# PlusBit_ExtraModule.net
KiCad netlist of a schematic drawn in Altium Designer
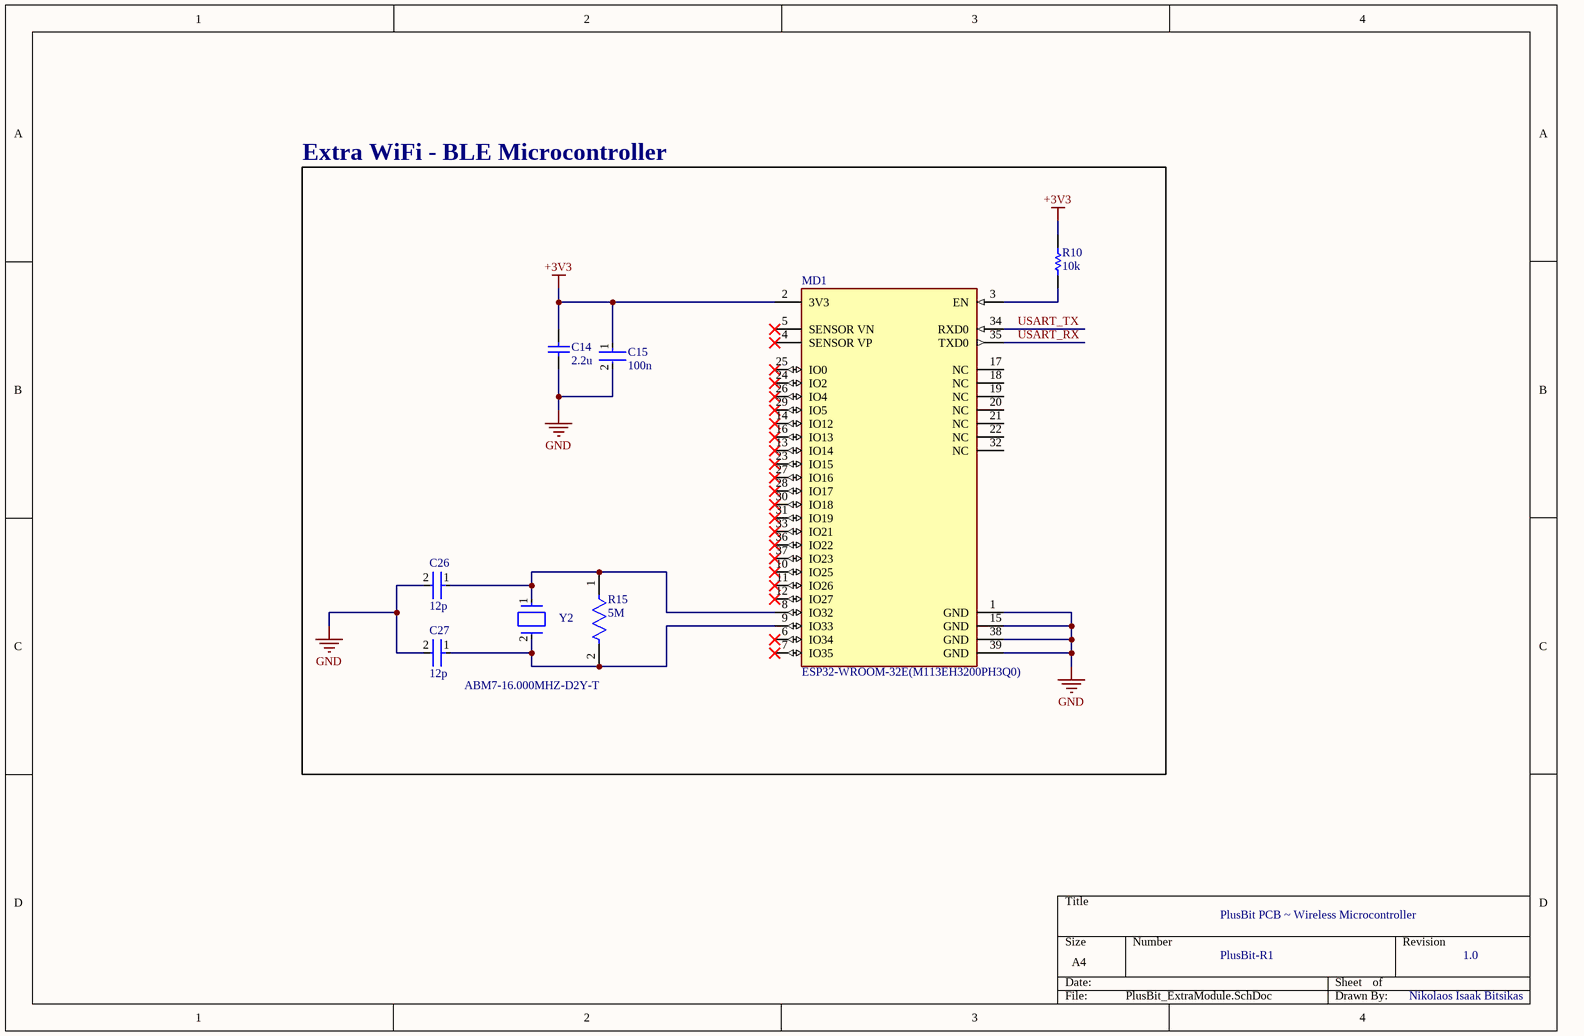
[diagram p0: PlusBit_ExtraModule.SchDoc]

(export (version "E")
  (design (tool "Eeschema 10.0.6"))
  (components
    (comp (ref "C14")
      (value "2.2u")
      (footprint "CAPC2013X145X50ML20T25")
      (fields (field (name "PART NUMBER") "C0805C225K9PACTU") (field (name "MANUFACTURER") "Kemet"))
      (libsource (lib "Altium Content Vault") (part "CAP"))
    )
    (comp (ref "C15")
      (value "100n")
      (footprint "FP-C0402-BB-MFG")
      (description "CAP CER 0.1UF 10V X5R 0402")
      (fields (field (name "MANUFACTURER") "Kemet") (field (name "TOLERANCE") "0.1"))
      (libsource (lib "Altium Content Vault") (part "b4654b650e69147ec39a6b967a45e02"))
    )
    (comp (ref "C26")
      (value "12p")
      (footprint "FP-C0402-BB-MFG")
      (description "CAP CER 12PF 50V C0G/NP0 0402")
      (fields
        (field (name "OCTOPART") "https://octopart.com/c0402c120j5gactu-kemet-141377")
        (field (name "MANUFACTURER PART NUMBER") "C0402C120J5GACTU")
      )
      (libsource (lib "Altium Content Vault") (part "b4654b650e69147ec39a6b967a45e02"))
    )
    (comp (ref "C27")
      (value "12p")
      (footprint "FP-C0402-BB-MFG")
      (description "CAP CER 12PF 50V C0G/NP0 0402")
      (fields
        (field (name "OCTOPART") "https://octopart.com/c0402c120j5gactu-kemet-141377")
        (field (name "MANUFACTURER PART NUMBER") "C0402C120J5GACTU")
      )
      (libsource (lib "Altium Content Vault") (part "b4654b650e69147ec39a6b967a45e02"))
    )
    (comp (ref "MD1")
      (value "ESP32-WROOM-32E(M113EH3200PH3Q0)")
      (footprint "FP-ESP32-WROOM-32E_M113EH-MFG")
      (description "RX TXRX MOD WIFI TRACE ANT SMD")
      (libsource (lib "Altium Content Vault") (part "a4840fbd16b6d3d8633d6b8ddc62dfb"))
    )
    (comp (ref "R10")
      (value "10k")
      (footprint "RESC1608X55X25ML10T15")
      (description "Resistor, 10 KOhm, +/- 5%, 100 mW, -55 to 155 degC, 0603 (1608 Metric), RoHS, Tape and Reel")
      (fields (field (name "MANUFACTURER") "Yageo") (field (name "TOLERANCE") "5%"))
      (libsource (lib "Altium Content Vault") (part "RES-2"))
    )
    (comp (ref "R15")
      (value "5M")
      (footprint "FP-WSLP0805-MFG")
      (description "RES 0.005 OHM 1% 1W 0805")
      (fields (field (name "TOLERANCE") "1%"))
      (libsource (lib "Altium Content Vault") (part "1029c3af85768c4190bb7ad29bc67b5"))
    )
    (comp (ref "Y2")
      (value "ABM7-16.000MHZ-D2Y-T")
      (footprint "FP-ABM7-MFG")
      (description "Crystal 16MHz ±20ppm 18pF SMD-2 6mm x 3.5mm")
      (fields (field (name "TOLERANCE") "20ppm"))
      (libsource (lib "Altium Content Vault") (part "c23a69dc6c9e2f18f2079038eb95dd1"))
    )
  )
  (nets
    (net (code "1") (name "+3V3") (class "Default")
      (node (ref "C14") (pin "2") (pinfunction "2_2") (pintype "passive"))
      (node (ref "C15") (pin "1") (pinfunction "1_1") (pintype "passive"))
      (node (ref "MD1") (pin "2") (pinfunction "3V3_2") (pintype "power_in"))
      (node (ref "R10") (pin "2") (pinfunction "2_2") (pintype "passive"))
    )
    (net (code "2") (name "/USART_RX") (class "Default")
      (node (ref "MD1") (pin "35") (pinfunction "TXD0_35") (pintype "output"))
    )
    (net (code "3") (name "/USART_TX") (class "Default")
      (node (ref "MD1") (pin "34") (pinfunction "RXD0_34") (pintype "input"))
    )
    (net (code "4") (name "GND") (class "Default")
      (node (ref "C14") (pin "1") (pinfunction "1_1") (pintype "passive"))
      (node (ref "C15") (pin "2") (pinfunction "2_2") (pintype "passive"))
      (node (ref "C26") (pin "2") (pinfunction "2_2") (pintype "passive"))
      (node (ref "C27") (pin "2") (pinfunction "2_2") (pintype "passive"))
      (node (ref "MD1") (pin "1") (pinfunction "GND_1") (pintype "power_in"))
      (node (ref "MD1") (pin "15") (pinfunction "GND_15") (pintype "power_in"))
      (node (ref "MD1") (pin "38") (pinfunction "GND_38") (pintype "power_in"))
      (node (ref "MD1") (pin "39") (pinfunction "GND_39") (pintype "power_in"))
    )
    (net (code "5") (name "Net-(MD1-EN)") (class "Default")
      (node (ref "MD1") (pin "3") (pinfunction "EN_3") (pintype "input"))
      (node (ref "R10") (pin "1") (pinfunction "1_1") (pintype "passive"))
    )
    (net (code "6") (name "Net-(MD1-IO32)") (class "Default")
      (node (ref "C26") (pin "1") (pinfunction "1_1") (pintype "passive"))
      (node (ref "MD1") (pin "8") (pinfunction "IO32_8") (pintype "bidirectional"))
      (node (ref "R15") (pin "1") (pinfunction "1_1") (pintype "passive"))
      (node (ref "Y2") (pin "1") (pinfunction "1_1") (pintype "passive"))
    )
    (net (code "7") (name "Net-(MD1-IO33)") (class "Default")
      (node (ref "C27") (pin "1") (pinfunction "1_1") (pintype "passive"))
      (node (ref "MD1") (pin "9") (pinfunction "IO33_9") (pintype "bidirectional"))
      (node (ref "R15") (pin "2") (pinfunction "2_2") (pintype "passive"))
      (node (ref "Y2") (pin "2") (pinfunction "2_2") (pintype "passive"))
    )
    (net (code "8") (name "unconnected-(MD1-IO0-Pad25)") (class "Default")
      (node (ref "MD1") (pin "25") (pinfunction "IO0_25") (pintype "bidirectional+no_connect"))
    )
    (net (code "9") (name "unconnected-(MD1-IO2-Pad24)") (class "Default")
      (node (ref "MD1") (pin "24") (pinfunction "IO2_24") (pintype "bidirectional+no_connect"))
    )
    (net (code "10") (name "unconnected-(MD1-IO4-Pad26)") (class "Default")
      (node (ref "MD1") (pin "26") (pinfunction "IO4_26") (pintype "bidirectional+no_connect"))
    )
    (net (code "11") (name "unconnected-(MD1-IO5-Pad29)") (class "Default")
      (node (ref "MD1") (pin "29") (pinfunction "IO5_29") (pintype "bidirectional+no_connect"))
    )
    (net (code "12") (name "unconnected-(MD1-IO12-Pad14)") (class "Default")
      (node (ref "MD1") (pin "14") (pinfunction "IO12_14") (pintype "bidirectional+no_connect"))
    )
    (net (code "13") (name "unconnected-(MD1-IO13-Pad16)") (class "Default")
      (node (ref "MD1") (pin "16") (pinfunction "IO13_16") (pintype "bidirectional+no_connect"))
    )
    (net (code "14") (name "unconnected-(MD1-IO14-Pad13)") (class "Default")
      (node (ref "MD1") (pin "13") (pinfunction "IO14_13") (pintype "bidirectional+no_connect"))
    )
    (net (code "15") (name "unconnected-(MD1-IO15-Pad23)") (class "Default")
      (node (ref "MD1") (pin "23") (pinfunction "IO15_23") (pintype "bidirectional+no_connect"))
    )
    (net (code "16") (name "unconnected-(MD1-IO16-Pad27)") (class "Default")
      (node (ref "MD1") (pin "27") (pinfunction "IO16_27") (pintype "bidirectional+no_connect"))
    )
    (net (code "17") (name "unconnected-(MD1-IO17-Pad28)") (class "Default")
      (node (ref "MD1") (pin "28") (pinfunction "IO17_28") (pintype "bidirectional+no_connect"))
    )
    (net (code "18") (name "unconnected-(MD1-IO18-Pad30)") (class "Default")
      (node (ref "MD1") (pin "30") (pinfunction "IO18_30") (pintype "bidirectional+no_connect"))
    )
    (net (code "19") (name "unconnected-(MD1-IO19-Pad31)") (class "Default")
      (node (ref "MD1") (pin "31") (pinfunction "IO19_31") (pintype "bidirectional+no_connect"))
    )
    (net (code "20") (name "unconnected-(MD1-IO21-Pad33)") (class "Default")
      (node (ref "MD1") (pin "33") (pinfunction "IO21_33") (pintype "bidirectional+no_connect"))
    )
    (net (code "21") (name "unconnected-(MD1-IO22-Pad36)") (class "Default")
      (node (ref "MD1") (pin "36") (pinfunction "IO22_36") (pintype "bidirectional+no_connect"))
    )
    (net (code "22") (name "unconnected-(MD1-IO23-Pad37)") (class "Default")
      (node (ref "MD1") (pin "37") (pinfunction "IO23_37") (pintype "bidirectional+no_connect"))
    )
    (net (code "23") (name "unconnected-(MD1-IO25-Pad10)") (class "Default")
      (node (ref "MD1") (pin "10") (pinfunction "IO25_10") (pintype "bidirectional+no_connect"))
    )
    (net (code "24") (name "unconnected-(MD1-IO26-Pad11)") (class "Default")
      (node (ref "MD1") (pin "11") (pinfunction "IO26_11") (pintype "bidirectional+no_connect"))
    )
    (net (code "25") (name "unconnected-(MD1-IO27-Pad12)") (class "Default")
      (node (ref "MD1") (pin "12") (pinfunction "IO27_12") (pintype "bidirectional+no_connect"))
    )
    (net (code "26") (name "unconnected-(MD1-IO34-Pad6)") (class "Default")
      (node (ref "MD1") (pin "6") (pinfunction "IO34_6") (pintype "bidirectional+no_connect"))
    )
    (net (code "27") (name "unconnected-(MD1-IO35-Pad7)") (class "Default")
      (node (ref "MD1") (pin "7") (pinfunction "IO35_7") (pintype "bidirectional+no_connect"))
    )
    (net (code "28") (name "unconnected-(MD1-NC-Pad17)") (class "Default")
      (node (ref "MD1") (pin "17") (pinfunction "NC_17") (pintype "passive"))
    )
    (net (code "29") (name "unconnected-(MD1-NC-Pad18)") (class "Default")
      (node (ref "MD1") (pin "18") (pinfunction "NC_18") (pintype "passive"))
    )
    (net (code "30") (name "unconnected-(MD1-NC-Pad19)") (class "Default")
      (node (ref "MD1") (pin "19") (pinfunction "NC_19") (pintype "passive"))
    )
    (net (code "31") (name "unconnected-(MD1-NC-Pad20)") (class "Default")
      (node (ref "MD1") (pin "20") (pinfunction "NC_20") (pintype "passive"))
    )
    (net (code "32") (name "unconnected-(MD1-NC-Pad21)") (class "Default")
      (node (ref "MD1") (pin "21") (pinfunction "NC_21") (pintype "passive"))
    )
    (net (code "33") (name "unconnected-(MD1-NC-Pad22)") (class "Default")
      (node (ref "MD1") (pin "22") (pinfunction "NC_22") (pintype "passive"))
    )
    (net (code "34") (name "unconnected-(MD1-NC-Pad32)") (class "Default")
      (node (ref "MD1") (pin "32") (pinfunction "NC_32") (pintype "passive"))
    )
    (net (code "35") (name "unconnected-(MD1-SENSOR_VN-Pad5)") (class "Default")
      (node (ref "MD1") (pin "5") (pinfunction "SENSOR_VN_5") (pintype "passive+no_connect"))
    )
    (net (code "36") (name "unconnected-(MD1-SENSOR_VP-Pad4)") (class "Default")
      (node (ref "MD1") (pin "4") (pinfunction "SENSOR_VP_4") (pintype "passive+no_connect"))
    )
  )
)
